# TSOP-II-44_v2.net
KiCad netlist of a schematic drawn in EAGLE
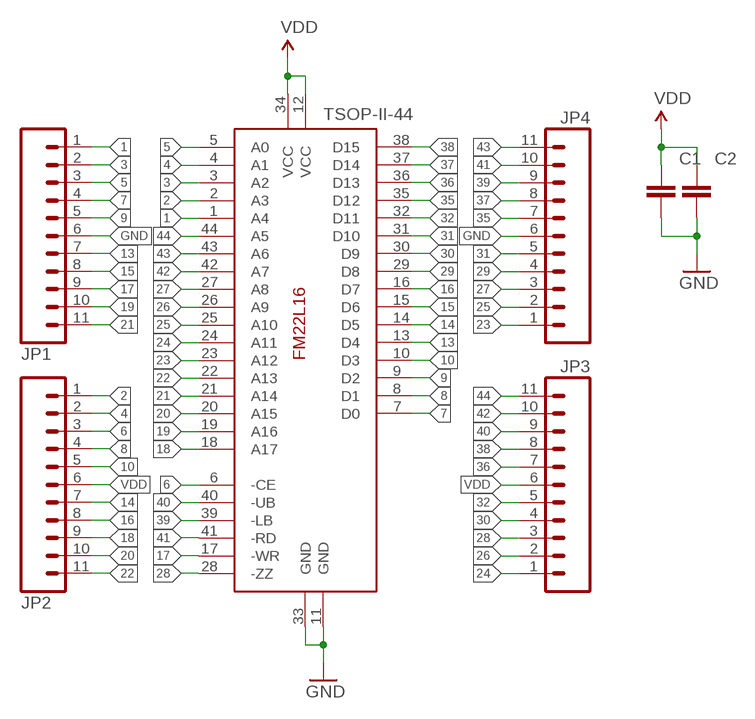
[diagram p0: schematic, sheet 1]

(export (version "E")
  (design (tool "Eeschema 10.0.6"))
  (components
    (comp (ref "C1")
      (value "CAPACITOR_NPOL-0603")
      (footprint "eagle-import:C603")
      (libsource (lib "eagle-import") (part "CAPACITOR_NPOL-0603"))
    )
    (comp (ref "C2")
      (value "CAPACITOR_NPOL-0603")
      (footprint "eagle-import:C603")
      (libsource (lib "eagle-import") (part "CAPACITOR_NPOL-0603"))
    )
    (comp (ref "JP1")
      (value "M11PTH")
      (footprint "eagle-import:1X11")
      (libsource (lib "eagle-import") (part "M11PTH"))
    )
    (comp (ref "JP2")
      (value "M11PTH")
      (footprint "eagle-import:1X11")
      (libsource (lib "eagle-import") (part "M11PTH"))
    )
    (comp (ref "JP3")
      (value "M11PTH")
      (footprint "eagle-import:1X11")
      (libsource (lib "eagle-import") (part "M11PTH"))
    )
    (comp (ref "JP4")
      (value "M11PTH")
      (footprint "eagle-import:1X11")
      (libsource (lib "eagle-import") (part "M11PTH"))
    )
    (comp (ref "TSOP-II-44")
      (value "FM22L16-TG")
      (footprint "eagle-import:TSOPII-44")
      (libsource (lib "eagle-import") (part "FM22L16-TG"))
    )
  )
  (nets
    (net (code "1") (name "1") (class "Default")
      (node (ref "JP1") (pin "1") (pinfunction "1_1") (pintype "passive"))
      (node (ref "TSOP-II-44") (pin "1") (pinfunction "A4_1") (pintype "input"))
    )
    (net (code "2") (name "2") (class "Default")
      (node (ref "JP2") (pin "1") (pinfunction "1_1") (pintype "passive"))
      (node (ref "TSOP-II-44") (pin "2") (pinfunction "A3_2") (pintype "input"))
    )
    (net (code "3") (name "3") (class "Default")
      (node (ref "JP1") (pin "2") (pinfunction "2_2") (pintype "passive"))
      (node (ref "TSOP-II-44") (pin "3") (pinfunction "A2_3") (pintype "input"))
    )
    (net (code "4") (name "4") (class "Default")
      (node (ref "JP2") (pin "2") (pinfunction "2_2") (pintype "passive"))
      (node (ref "TSOP-II-44") (pin "4") (pinfunction "A1_4") (pintype "input"))
    )
    (net (code "5") (name "5") (class "Default")
      (node (ref "JP1") (pin "3") (pinfunction "3_3") (pintype "passive"))
      (node (ref "TSOP-II-44") (pin "5") (pinfunction "A0_5") (pintype "input"))
    )
    (net (code "6") (name "6") (class "Default")
      (node (ref "JP2") (pin "3") (pinfunction "3_3") (pintype "passive"))
      (node (ref "TSOP-II-44") (pin "6") (pinfunction "-CE_6") (pintype "input"))
    )
    (net (code "7") (name "7") (class "Default")
      (node (ref "JP1") (pin "4") (pinfunction "4_4") (pintype "passive"))
      (node (ref "TSOP-II-44") (pin "7") (pinfunction "D0_7") (pintype "bidirectional"))
    )
    (net (code "8") (name "8") (class "Default")
      (node (ref "JP2") (pin "4") (pinfunction "4_4") (pintype "passive"))
      (node (ref "TSOP-II-44") (pin "8") (pinfunction "D1_8") (pintype "bidirectional"))
    )
    (net (code "9") (name "9") (class "Default")
      (node (ref "JP1") (pin "5") (pinfunction "5_5") (pintype "passive"))
      (node (ref "TSOP-II-44") (pin "9") (pinfunction "D2_9") (pintype "bidirectional"))
    )
    (net (code "10") (name "10") (class "Default")
      (node (ref "JP2") (pin "5") (pinfunction "5_5") (pintype "passive"))
      (node (ref "TSOP-II-44") (pin "10") (pinfunction "D3_10") (pintype "bidirectional"))
    )
    (net (code "11") (name "13") (class "Default")
      (node (ref "JP1") (pin "7") (pinfunction "7_7") (pintype "passive"))
      (node (ref "TSOP-II-44") (pin "13") (pinfunction "D4_13") (pintype "bidirectional"))
    )
    (net (code "12") (name "14") (class "Default")
      (node (ref "JP2") (pin "7") (pinfunction "7_7") (pintype "passive"))
      (node (ref "TSOP-II-44") (pin "14") (pinfunction "D5_14") (pintype "bidirectional"))
    )
    (net (code "13") (name "15") (class "Default")
      (node (ref "JP1") (pin "8") (pinfunction "8_8") (pintype "passive"))
      (node (ref "TSOP-II-44") (pin "15") (pinfunction "D6_15") (pintype "bidirectional"))
    )
    (net (code "14") (name "16") (class "Default")
      (node (ref "JP2") (pin "8") (pinfunction "8_8") (pintype "passive"))
      (node (ref "TSOP-II-44") (pin "16") (pinfunction "D7_16") (pintype "bidirectional"))
    )
    (net (code "15") (name "17") (class "Default")
      (node (ref "JP1") (pin "9") (pinfunction "9_9") (pintype "passive"))
      (node (ref "TSOP-II-44") (pin "17") (pinfunction "-WR_17") (pintype "input"))
    )
    (net (code "16") (name "18") (class "Default")
      (node (ref "JP2") (pin "9") (pinfunction "9_9") (pintype "passive"))
      (node (ref "TSOP-II-44") (pin "18") (pinfunction "A17_18") (pintype "input"))
    )
    (net (code "17") (name "19") (class "Default")
      (node (ref "JP1") (pin "10") (pinfunction "10_10") (pintype "passive"))
      (node (ref "TSOP-II-44") (pin "19") (pinfunction "A16_19") (pintype "input"))
    )
    (net (code "18") (name "20") (class "Default")
      (node (ref "JP2") (pin "10") (pinfunction "10_10") (pintype "passive"))
      (node (ref "TSOP-II-44") (pin "20") (pinfunction "A15_20") (pintype "input"))
    )
    (net (code "19") (name "21") (class "Default")
      (node (ref "JP1") (pin "11") (pinfunction "11_11") (pintype "passive"))
      (node (ref "TSOP-II-44") (pin "21") (pinfunction "A14_21") (pintype "input"))
    )
    (net (code "20") (name "22") (class "Default")
      (node (ref "JP2") (pin "11") (pinfunction "11_11") (pintype "passive"))
      (node (ref "TSOP-II-44") (pin "22") (pinfunction "A13_22") (pintype "input"))
    )
    (net (code "21") (name "23") (class "Default")
      (node (ref "JP4") (pin "1") (pinfunction "1_1") (pintype "passive"))
      (node (ref "TSOP-II-44") (pin "23") (pinfunction "A12_23") (pintype "input"))
    )
    (net (code "22") (name "24") (class "Default")
      (node (ref "JP3") (pin "1") (pinfunction "1_1") (pintype "passive"))
      (node (ref "TSOP-II-44") (pin "24") (pinfunction "A11_24") (pintype "input"))
    )
    (net (code "23") (name "25") (class "Default")
      (node (ref "JP4") (pin "2") (pinfunction "2_2") (pintype "passive"))
      (node (ref "TSOP-II-44") (pin "25") (pinfunction "A10_25") (pintype "input"))
    )
    (net (code "24") (name "26") (class "Default")
      (node (ref "JP3") (pin "2") (pinfunction "2_2") (pintype "passive"))
      (node (ref "TSOP-II-44") (pin "26") (pinfunction "A9_26") (pintype "input"))
    )
    (net (code "25") (name "27") (class "Default")
      (node (ref "JP4") (pin "3") (pinfunction "3_3") (pintype "passive"))
      (node (ref "TSOP-II-44") (pin "27") (pinfunction "A8_27") (pintype "input"))
    )
    (net (code "26") (name "28") (class "Default")
      (node (ref "JP3") (pin "3") (pinfunction "3_3") (pintype "passive"))
      (node (ref "TSOP-II-44") (pin "28") (pinfunction "-ZZ_28") (pintype "input"))
    )
    (net (code "27") (name "29") (class "Default")
      (node (ref "JP4") (pin "4") (pinfunction "4_4") (pintype "passive"))
      (node (ref "TSOP-II-44") (pin "29") (pinfunction "D8_29") (pintype "bidirectional"))
    )
    (net (code "28") (name "30") (class "Default")
      (node (ref "JP3") (pin "4") (pinfunction "4_4") (pintype "passive"))
      (node (ref "TSOP-II-44") (pin "30") (pinfunction "D9_30") (pintype "bidirectional"))
    )
    (net (code "29") (name "31") (class "Default")
      (node (ref "JP4") (pin "5") (pinfunction "5_5") (pintype "passive"))
      (node (ref "TSOP-II-44") (pin "31") (pinfunction "D10_31") (pintype "bidirectional"))
    )
    (net (code "30") (name "32") (class "Default")
      (node (ref "JP3") (pin "5") (pinfunction "5_5") (pintype "passive"))
      (node (ref "TSOP-II-44") (pin "32") (pinfunction "D11_32") (pintype "bidirectional"))
    )
    (net (code "31") (name "35") (class "Default")
      (node (ref "JP4") (pin "7") (pinfunction "7_7") (pintype "passive"))
      (node (ref "TSOP-II-44") (pin "35") (pinfunction "D12_35") (pintype "bidirectional"))
    )
    (net (code "32") (name "36") (class "Default")
      (node (ref "JP3") (pin "7") (pinfunction "7_7") (pintype "passive"))
      (node (ref "TSOP-II-44") (pin "36") (pinfunction "D13_36") (pintype "bidirectional"))
    )
    (net (code "33") (name "37") (class "Default")
      (node (ref "JP4") (pin "8") (pinfunction "8_8") (pintype "passive"))
      (node (ref "TSOP-II-44") (pin "37") (pinfunction "D14_37") (pintype "bidirectional"))
    )
    (net (code "34") (name "38") (class "Default")
      (node (ref "JP3") (pin "8") (pinfunction "8_8") (pintype "passive"))
      (node (ref "TSOP-II-44") (pin "38") (pinfunction "D15_38") (pintype "bidirectional"))
    )
    (net (code "35") (name "39") (class "Default")
      (node (ref "JP4") (pin "9") (pinfunction "9_9") (pintype "passive"))
      (node (ref "TSOP-II-44") (pin "39") (pinfunction "-LB_39") (pintype "input"))
    )
    (net (code "36") (name "40") (class "Default")
      (node (ref "JP3") (pin "9") (pinfunction "9_9") (pintype "passive"))
      (node (ref "TSOP-II-44") (pin "40") (pinfunction "-UB_40") (pintype "input"))
    )
    (net (code "37") (name "41") (class "Default")
      (node (ref "JP4") (pin "10") (pinfunction "10_10") (pintype "passive"))
      (node (ref "TSOP-II-44") (pin "41") (pinfunction "-RD_41") (pintype "input"))
    )
    (net (code "38") (name "42") (class "Default")
      (node (ref "JP3") (pin "10") (pinfunction "10_10") (pintype "passive"))
      (node (ref "TSOP-II-44") (pin "42") (pinfunction "A7_42") (pintype "input"))
    )
    (net (code "39") (name "43") (class "Default")
      (node (ref "JP4") (pin "11") (pinfunction "11_11") (pintype "passive"))
      (node (ref "TSOP-II-44") (pin "43") (pinfunction "A6_43") (pintype "input"))
    )
    (net (code "40") (name "44") (class "Default")
      (node (ref "JP3") (pin "11") (pinfunction "11_11") (pintype "passive"))
      (node (ref "TSOP-II-44") (pin "44") (pinfunction "A5_44") (pintype "input"))
    )
    (net (code "41") (name "GND") (class "Default")
      (node (ref "C1") (pin "2") (pinfunction "2_2") (pintype "passive"))
      (node (ref "C2") (pin "2") (pinfunction "2_2") (pintype "passive"))
      (node (ref "JP1") (pin "6") (pinfunction "6_6") (pintype "passive"))
      (node (ref "JP4") (pin "6") (pinfunction "6_6") (pintype "passive"))
      (node (ref "TSOP-II-44") (pin "11") (pinfunction "GND_11") (pintype "power_in"))
      (node (ref "TSOP-II-44") (pin "33") (pinfunction "GND_33") (pintype "power_in"))
    )
    (net (code "42") (name "VDD") (class "Default")
      (node (ref "C1") (pin "1") (pinfunction "1_1") (pintype "passive"))
      (node (ref "C2") (pin "1") (pinfunction "1_1") (pintype "passive"))
      (node (ref "JP2") (pin "6") (pinfunction "6_6") (pintype "passive"))
      (node (ref "JP3") (pin "6") (pinfunction "6_6") (pintype "passive"))
      (node (ref "TSOP-II-44") (pin "12") (pinfunction "VCC_12") (pintype "power_in"))
      (node (ref "TSOP-II-44") (pin "34") (pinfunction "VCC_34") (pintype "power_in"))
    )
  )
)
